# Sheet1.net
KiCad netlist of a schematic drawn in Altium Designer
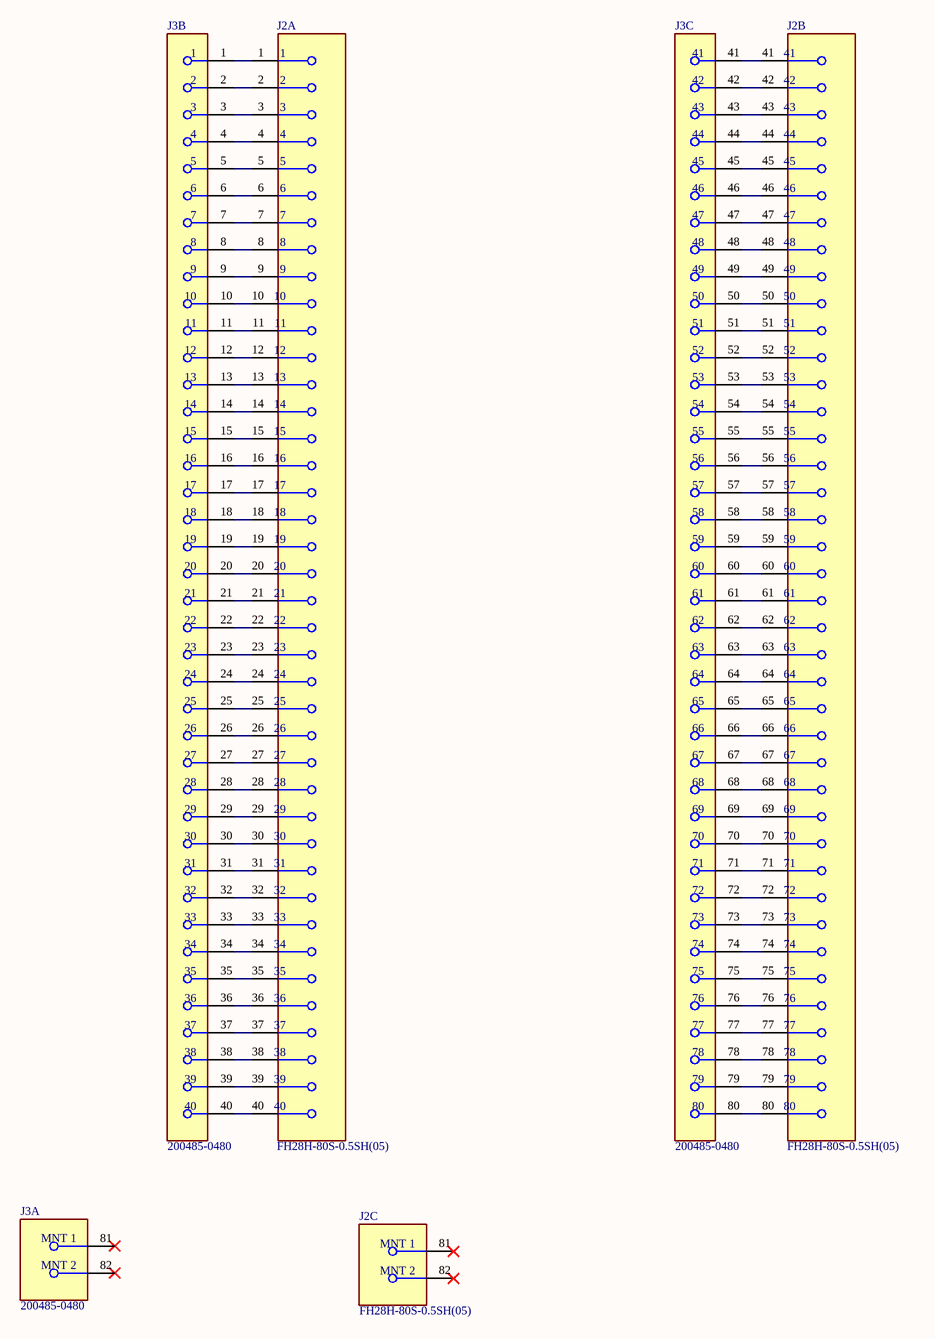
[diagram p0: Sheet1.SchDoc]

(export (version "E")
  (design (tool "Eeschema 10.0.6"))
  (components
    (comp (ref "J2")
      (value "FH28H-80S-0.5SH(05)")
      (footprint "FP-FH28H-80S-0_5SH_05-MFG")
      (description "CONN FFC BOTTOM 80POS 0.50MM R/A")
      (libsource (lib "") (part "08075b3669470a400ec152efcfe4938_1"))
    )
    (comp (ref "J3")
      (value "200485-0480")
      (footprint "FP-200485-0480-MFG")
      (description "0.5 ONE-TOUCH RA 80P")
      (libsource (lib "Altium Content Vault") (part "c44dc25a27ac546c6585fccd4967c56"))
    )
  )
  (nets
    (net (code "1") (name "Net-(J2-Pad1)") (class "Default")
      (node (ref "J2") (pin "1") (pinfunction "1_1") (pintype "passive"))
      (node (ref "J3") (pin "1") (pinfunction "1_1") (pintype "passive"))
    )
    (net (code "2") (name "Net-(J2-Pad2)") (class "Default")
      (node (ref "J2") (pin "2") (pinfunction "2_2") (pintype "passive"))
      (node (ref "J3") (pin "2") (pinfunction "2_2") (pintype "passive"))
    )
    (net (code "3") (name "Net-(J2-Pad3)") (class "Default")
      (node (ref "J2") (pin "3") (pinfunction "3_3") (pintype "passive"))
      (node (ref "J3") (pin "3") (pinfunction "3_3") (pintype "passive"))
    )
    (net (code "4") (name "Net-(J2-Pad4)") (class "Default")
      (node (ref "J2") (pin "4") (pinfunction "4_4") (pintype "passive"))
      (node (ref "J3") (pin "4") (pinfunction "4_4") (pintype "passive"))
    )
    (net (code "5") (name "Net-(J2-Pad5)") (class "Default")
      (node (ref "J2") (pin "5") (pinfunction "5_5") (pintype "passive"))
      (node (ref "J3") (pin "5") (pinfunction "5_5") (pintype "passive"))
    )
    (net (code "6") (name "Net-(J2-Pad6)") (class "Default")
      (node (ref "J2") (pin "6") (pinfunction "6_6") (pintype "passive"))
      (node (ref "J3") (pin "6") (pinfunction "6_6") (pintype "passive"))
    )
    (net (code "7") (name "Net-(J2-Pad7)") (class "Default")
      (node (ref "J2") (pin "7") (pinfunction "7_7") (pintype "passive"))
      (node (ref "J3") (pin "7") (pinfunction "7_7") (pintype "passive"))
    )
    (net (code "8") (name "Net-(J2-Pad8)") (class "Default")
      (node (ref "J2") (pin "8") (pinfunction "8_8") (pintype "passive"))
      (node (ref "J3") (pin "8") (pinfunction "8_8") (pintype "passive"))
    )
    (net (code "9") (name "Net-(J2-Pad9)") (class "Default")
      (node (ref "J2") (pin "9") (pinfunction "9_9") (pintype "passive"))
      (node (ref "J3") (pin "9") (pinfunction "9_9") (pintype "passive"))
    )
    (net (code "10") (name "Net-(J2-Pad10)") (class "Default")
      (node (ref "J2") (pin "10") (pinfunction "10_10") (pintype "passive"))
      (node (ref "J3") (pin "10") (pinfunction "10_10") (pintype "passive"))
    )
    (net (code "11") (name "Net-(J2-Pad11)") (class "Default")
      (node (ref "J2") (pin "11") (pinfunction "11_11") (pintype "passive"))
      (node (ref "J3") (pin "11") (pinfunction "11_11") (pintype "passive"))
    )
    (net (code "12") (name "Net-(J2-Pad12)") (class "Default")
      (node (ref "J2") (pin "12") (pinfunction "12_12") (pintype "passive"))
      (node (ref "J3") (pin "12") (pinfunction "12_12") (pintype "passive"))
    )
    (net (code "13") (name "Net-(J2-Pad13)") (class "Default")
      (node (ref "J2") (pin "13") (pinfunction "13_13") (pintype "passive"))
      (node (ref "J3") (pin "13") (pinfunction "13_13") (pintype "passive"))
    )
    (net (code "14") (name "Net-(J2-Pad14)") (class "Default")
      (node (ref "J2") (pin "14") (pinfunction "14_14") (pintype "passive"))
      (node (ref "J3") (pin "14") (pinfunction "14_14") (pintype "passive"))
    )
    (net (code "15") (name "Net-(J2-Pad15)") (class "Default")
      (node (ref "J2") (pin "15") (pinfunction "15_15") (pintype "passive"))
      (node (ref "J3") (pin "15") (pinfunction "15_15") (pintype "passive"))
    )
    (net (code "16") (name "Net-(J2-Pad16)") (class "Default")
      (node (ref "J2") (pin "16") (pinfunction "16_16") (pintype "passive"))
      (node (ref "J3") (pin "16") (pinfunction "16_16") (pintype "passive"))
    )
    (net (code "17") (name "Net-(J2-Pad17)") (class "Default")
      (node (ref "J2") (pin "17") (pinfunction "17_17") (pintype "passive"))
      (node (ref "J3") (pin "17") (pinfunction "17_17") (pintype "passive"))
    )
    (net (code "18") (name "Net-(J2-Pad18)") (class "Default")
      (node (ref "J2") (pin "18") (pinfunction "18_18") (pintype "passive"))
      (node (ref "J3") (pin "18") (pinfunction "18_18") (pintype "passive"))
    )
    (net (code "19") (name "Net-(J2-Pad19)") (class "Default")
      (node (ref "J2") (pin "19") (pinfunction "19_19") (pintype "passive"))
      (node (ref "J3") (pin "19") (pinfunction "19_19") (pintype "passive"))
    )
    (net (code "20") (name "Net-(J2-Pad20)") (class "Default")
      (node (ref "J2") (pin "20") (pinfunction "20_20") (pintype "passive"))
      (node (ref "J3") (pin "20") (pinfunction "20_20") (pintype "passive"))
    )
    (net (code "21") (name "Net-(J2-Pad21)") (class "Default")
      (node (ref "J2") (pin "21") (pinfunction "21_21") (pintype "passive"))
      (node (ref "J3") (pin "21") (pinfunction "21_21") (pintype "passive"))
    )
    (net (code "22") (name "Net-(J2-Pad22)") (class "Default")
      (node (ref "J2") (pin "22") (pinfunction "22_22") (pintype "passive"))
      (node (ref "J3") (pin "22") (pinfunction "22_22") (pintype "passive"))
    )
    (net (code "23") (name "Net-(J2-Pad23)") (class "Default")
      (node (ref "J2") (pin "23") (pinfunction "23_23") (pintype "passive"))
      (node (ref "J3") (pin "23") (pinfunction "23_23") (pintype "passive"))
    )
    (net (code "24") (name "Net-(J2-Pad24)") (class "Default")
      (node (ref "J2") (pin "24") (pinfunction "24_24") (pintype "passive"))
      (node (ref "J3") (pin "24") (pinfunction "24_24") (pintype "passive"))
    )
    (net (code "25") (name "Net-(J2-Pad25)") (class "Default")
      (node (ref "J2") (pin "25") (pinfunction "25_25") (pintype "passive"))
      (node (ref "J3") (pin "25") (pinfunction "25_25") (pintype "passive"))
    )
    (net (code "26") (name "Net-(J2-Pad26)") (class "Default")
      (node (ref "J2") (pin "26") (pinfunction "26_26") (pintype "passive"))
      (node (ref "J3") (pin "26") (pinfunction "26_26") (pintype "passive"))
    )
    (net (code "27") (name "Net-(J2-Pad27)") (class "Default")
      (node (ref "J2") (pin "27") (pinfunction "27_27") (pintype "passive"))
      (node (ref "J3") (pin "27") (pinfunction "27_27") (pintype "passive"))
    )
    (net (code "28") (name "Net-(J2-Pad28)") (class "Default")
      (node (ref "J2") (pin "28") (pinfunction "28_28") (pintype "passive"))
      (node (ref "J3") (pin "28") (pinfunction "28_28") (pintype "passive"))
    )
    (net (code "29") (name "Net-(J2-Pad29)") (class "Default")
      (node (ref "J2") (pin "29") (pinfunction "29_29") (pintype "passive"))
      (node (ref "J3") (pin "29") (pinfunction "29_29") (pintype "passive"))
    )
    (net (code "30") (name "Net-(J2-Pad30)") (class "Default")
      (node (ref "J2") (pin "30") (pinfunction "30_30") (pintype "passive"))
      (node (ref "J3") (pin "30") (pinfunction "30_30") (pintype "passive"))
    )
    (net (code "31") (name "Net-(J2-Pad31)") (class "Default")
      (node (ref "J2") (pin "31") (pinfunction "31_31") (pintype "passive"))
      (node (ref "J3") (pin "31") (pinfunction "31_31") (pintype "passive"))
    )
    (net (code "32") (name "Net-(J2-Pad32)") (class "Default")
      (node (ref "J2") (pin "32") (pinfunction "32_32") (pintype "passive"))
      (node (ref "J3") (pin "32") (pinfunction "32_32") (pintype "passive"))
    )
    (net (code "33") (name "Net-(J2-Pad33)") (class "Default")
      (node (ref "J2") (pin "33") (pinfunction "33_33") (pintype "passive"))
      (node (ref "J3") (pin "33") (pinfunction "33_33") (pintype "passive"))
    )
    (net (code "34") (name "Net-(J2-Pad34)") (class "Default")
      (node (ref "J2") (pin "34") (pinfunction "34_34") (pintype "passive"))
      (node (ref "J3") (pin "34") (pinfunction "34_34") (pintype "passive"))
    )
    (net (code "35") (name "Net-(J2-Pad35)") (class "Default")
      (node (ref "J2") (pin "35") (pinfunction "35_35") (pintype "passive"))
      (node (ref "J3") (pin "35") (pinfunction "35_35") (pintype "passive"))
    )
    (net (code "36") (name "Net-(J2-Pad36)") (class "Default")
      (node (ref "J2") (pin "36") (pinfunction "36_36") (pintype "passive"))
      (node (ref "J3") (pin "36") (pinfunction "36_36") (pintype "passive"))
    )
    (net (code "37") (name "Net-(J2-Pad37)") (class "Default")
      (node (ref "J2") (pin "37") (pinfunction "37_37") (pintype "passive"))
      (node (ref "J3") (pin "37") (pinfunction "37_37") (pintype "passive"))
    )
    (net (code "38") (name "Net-(J2-Pad38)") (class "Default")
      (node (ref "J2") (pin "38") (pinfunction "38_38") (pintype "passive"))
      (node (ref "J3") (pin "38") (pinfunction "38_38") (pintype "passive"))
    )
    (net (code "39") (name "Net-(J2-Pad39)") (class "Default")
      (node (ref "J2") (pin "39") (pinfunction "39_39") (pintype "passive"))
      (node (ref "J3") (pin "39") (pinfunction "39_39") (pintype "passive"))
    )
    (net (code "40") (name "Net-(J2-Pad40)") (class "Default")
      (node (ref "J2") (pin "40") (pinfunction "40_40") (pintype "passive"))
      (node (ref "J3") (pin "40") (pinfunction "40_40") (pintype "passive"))
    )
    (net (code "41") (name "Net-(J2-Pad41)") (class "Default")
      (node (ref "J2") (pin "41") (pinfunction "41_41") (pintype "passive"))
      (node (ref "J3") (pin "41") (pinfunction "41_41") (pintype "passive"))
    )
    (net (code "42") (name "Net-(J2-Pad42)") (class "Default")
      (node (ref "J2") (pin "42") (pinfunction "42_42") (pintype "passive"))
      (node (ref "J3") (pin "42") (pinfunction "42_42") (pintype "passive"))
    )
    (net (code "43") (name "Net-(J2-Pad43)") (class "Default")
      (node (ref "J2") (pin "43") (pinfunction "43_43") (pintype "passive"))
      (node (ref "J3") (pin "43") (pinfunction "43_43") (pintype "passive"))
    )
    (net (code "44") (name "Net-(J2-Pad44)") (class "Default")
      (node (ref "J2") (pin "44") (pinfunction "44_44") (pintype "passive"))
      (node (ref "J3") (pin "44") (pinfunction "44_44") (pintype "passive"))
    )
    (net (code "45") (name "Net-(J2-Pad45)") (class "Default")
      (node (ref "J2") (pin "45") (pinfunction "45_45") (pintype "passive"))
      (node (ref "J3") (pin "45") (pinfunction "45_45") (pintype "passive"))
    )
    (net (code "46") (name "Net-(J2-Pad46)") (class "Default")
      (node (ref "J2") (pin "46") (pinfunction "46_46") (pintype "passive"))
      (node (ref "J3") (pin "46") (pinfunction "46_46") (pintype "passive"))
    )
    (net (code "47") (name "Net-(J2-Pad47)") (class "Default")
      (node (ref "J2") (pin "47") (pinfunction "47_47") (pintype "passive"))
      (node (ref "J3") (pin "47") (pinfunction "47_47") (pintype "passive"))
    )
    (net (code "48") (name "Net-(J2-Pad48)") (class "Default")
      (node (ref "J2") (pin "48") (pinfunction "48_48") (pintype "passive"))
      (node (ref "J3") (pin "48") (pinfunction "48_48") (pintype "passive"))
    )
    (net (code "49") (name "Net-(J2-Pad49)") (class "Default")
      (node (ref "J2") (pin "49") (pinfunction "49_49") (pintype "passive"))
      (node (ref "J3") (pin "49") (pinfunction "49_49") (pintype "passive"))
    )
    (net (code "50") (name "Net-(J2-Pad50)") (class "Default")
      (node (ref "J2") (pin "50") (pinfunction "50_50") (pintype "passive"))
      (node (ref "J3") (pin "50") (pinfunction "50_50") (pintype "passive"))
    )
    (net (code "51") (name "Net-(J2-Pad51)") (class "Default")
      (node (ref "J2") (pin "51") (pinfunction "51_51") (pintype "passive"))
      (node (ref "J3") (pin "51") (pinfunction "51_51") (pintype "passive"))
    )
    (net (code "52") (name "Net-(J2-Pad52)") (class "Default")
      (node (ref "J2") (pin "52") (pinfunction "52_52") (pintype "passive"))
      (node (ref "J3") (pin "52") (pinfunction "52_52") (pintype "passive"))
    )
    (net (code "53") (name "Net-(J2-Pad53)") (class "Default")
      (node (ref "J2") (pin "53") (pinfunction "53_53") (pintype "passive"))
      (node (ref "J3") (pin "53") (pinfunction "53_53") (pintype "passive"))
    )
    (net (code "54") (name "Net-(J2-Pad54)") (class "Default")
      (node (ref "J2") (pin "54") (pinfunction "54_54") (pintype "passive"))
      (node (ref "J3") (pin "54") (pinfunction "54_54") (pintype "passive"))
    )
    (net (code "55") (name "Net-(J2-Pad55)") (class "Default")
      (node (ref "J2") (pin "55") (pinfunction "55_55") (pintype "passive"))
      (node (ref "J3") (pin "55") (pinfunction "55_55") (pintype "passive"))
    )
    (net (code "56") (name "Net-(J2-Pad56)") (class "Default")
      (node (ref "J2") (pin "56") (pinfunction "56_56") (pintype "passive"))
      (node (ref "J3") (pin "56") (pinfunction "56_56") (pintype "passive"))
    )
    (net (code "57") (name "Net-(J2-Pad57)") (class "Default")
      (node (ref "J2") (pin "57") (pinfunction "57_57") (pintype "passive"))
      (node (ref "J3") (pin "57") (pinfunction "57_57") (pintype "passive"))
    )
    (net (code "58") (name "Net-(J2-Pad58)") (class "Default")
      (node (ref "J2") (pin "58") (pinfunction "58_58") (pintype "passive"))
      (node (ref "J3") (pin "58") (pinfunction "58_58") (pintype "passive"))
    )
    (net (code "59") (name "Net-(J2-Pad59)") (class "Default")
      (node (ref "J2") (pin "59") (pinfunction "59_59") (pintype "passive"))
      (node (ref "J3") (pin "59") (pinfunction "59_59") (pintype "passive"))
    )
    (net (code "60") (name "Net-(J2-Pad60)") (class "Default")
      (node (ref "J2") (pin "60") (pinfunction "60_60") (pintype "passive"))
      (node (ref "J3") (pin "60") (pinfunction "60_60") (pintype "passive"))
    )
    (net (code "61") (name "Net-(J2-Pad61)") (class "Default")
      (node (ref "J2") (pin "61") (pinfunction "61_61") (pintype "passive"))
      (node (ref "J3") (pin "61") (pinfunction "61_61") (pintype "passive"))
    )
    (net (code "62") (name "Net-(J2-Pad62)") (class "Default")
      (node (ref "J2") (pin "62") (pinfunction "62_62") (pintype "passive"))
      (node (ref "J3") (pin "62") (pinfunction "62_62") (pintype "passive"))
    )
    (net (code "63") (name "Net-(J2-Pad63)") (class "Default")
      (node (ref "J2") (pin "63") (pinfunction "63_63") (pintype "passive"))
      (node (ref "J3") (pin "63") (pinfunction "63_63") (pintype "passive"))
    )
    (net (code "64") (name "Net-(J2-Pad64)") (class "Default")
      (node (ref "J2") (pin "64") (pinfunction "64_64") (pintype "passive"))
      (node (ref "J3") (pin "64") (pinfunction "64_64") (pintype "passive"))
    )
    (net (code "65") (name "Net-(J2-Pad65)") (class "Default")
      (node (ref "J2") (pin "65") (pinfunction "65_65") (pintype "passive"))
      (node (ref "J3") (pin "65") (pinfunction "65_65") (pintype "passive"))
    )
    (net (code "66") (name "Net-(J2-Pad66)") (class "Default")
      (node (ref "J2") (pin "66") (pinfunction "66_66") (pintype "passive"))
      (node (ref "J3") (pin "66") (pinfunction "66_66") (pintype "passive"))
    )
    (net (code "67") (name "Net-(J2-Pad67)") (class "Default")
      (node (ref "J2") (pin "67") (pinfunction "67_67") (pintype "passive"))
      (node (ref "J3") (pin "67") (pinfunction "67_67") (pintype "passive"))
    )
    (net (code "68") (name "Net-(J2-Pad68)") (class "Default")
      (node (ref "J2") (pin "68") (pinfunction "68_68") (pintype "passive"))
      (node (ref "J3") (pin "68") (pinfunction "68_68") (pintype "passive"))
    )
    (net (code "69") (name "Net-(J2-Pad69)") (class "Default")
      (node (ref "J2") (pin "69") (pinfunction "69_69") (pintype "passive"))
      (node (ref "J3") (pin "69") (pinfunction "69_69") (pintype "passive"))
    )
    (net (code "70") (name "Net-(J2-Pad70)") (class "Default")
      (node (ref "J2") (pin "70") (pinfunction "70_70") (pintype "passive"))
      (node (ref "J3") (pin "70") (pinfunction "70_70") (pintype "passive"))
    )
    (net (code "71") (name "Net-(J2-Pad71)") (class "Default")
      (node (ref "J2") (pin "71") (pinfunction "71_71") (pintype "passive"))
      (node (ref "J3") (pin "71") (pinfunction "71_71") (pintype "passive"))
    )
    (net (code "72") (name "Net-(J2-Pad72)") (class "Default")
      (node (ref "J2") (pin "72") (pinfunction "72_72") (pintype "passive"))
      (node (ref "J3") (pin "72") (pinfunction "72_72") (pintype "passive"))
    )
    (net (code "73") (name "Net-(J2-Pad73)") (class "Default")
      (node (ref "J2") (pin "73") (pinfunction "73_73") (pintype "passive"))
      (node (ref "J3") (pin "73") (pinfunction "73_73") (pintype "passive"))
    )
    (net (code "74") (name "Net-(J2-Pad74)") (class "Default")
      (node (ref "J2") (pin "74") (pinfunction "74_74") (pintype "passive"))
      (node (ref "J3") (pin "74") (pinfunction "74_74") (pintype "passive"))
    )
    (net (code "75") (name "Net-(J2-Pad75)") (class "Default")
      (node (ref "J2") (pin "75") (pinfunction "75_75") (pintype "passive"))
      (node (ref "J3") (pin "75") (pinfunction "75_75") (pintype "passive"))
    )
    (net (code "76") (name "Net-(J2-Pad76)") (class "Default")
      (node (ref "J2") (pin "76") (pinfunction "76_76") (pintype "passive"))
      (node (ref "J3") (pin "76") (pinfunction "76_76") (pintype "passive"))
    )
    (net (code "77") (name "Net-(J2-Pad77)") (class "Default")
      (node (ref "J2") (pin "77") (pinfunction "77_77") (pintype "passive"))
      (node (ref "J3") (pin "77") (pinfunction "77_77") (pintype "passive"))
    )
    (net (code "78") (name "Net-(J2-Pad78)") (class "Default")
      (node (ref "J2") (pin "78") (pinfunction "78_78") (pintype "passive"))
      (node (ref "J3") (pin "78") (pinfunction "78_78") (pintype "passive"))
    )
    (net (code "79") (name "Net-(J2-Pad79)") (class "Default")
      (node (ref "J2") (pin "79") (pinfunction "79_79") (pintype "passive"))
      (node (ref "J3") (pin "79") (pinfunction "79_79") (pintype "passive"))
    )
    (net (code "80") (name "Net-(J2-Pad80)") (class "Default")
      (node (ref "J2") (pin "80") (pinfunction "80_80") (pintype "passive"))
      (node (ref "J3") (pin "80") (pinfunction "80_80") (pintype "passive"))
    )
    (net (code "81") (name "unconnected-(J2C-MNT_1-Pad81)") (class "Default")
      (node (ref "J2") (pin "81") (pinfunction "MNT_1_81") (pintype "passive+no_connect"))
    )
    (net (code "82") (name "unconnected-(J2C-MNT_2-Pad82)") (class "Default")
      (node (ref "J2") (pin "82") (pinfunction "MNT_2_82") (pintype "passive+no_connect"))
    )
    (net (code "83") (name "unconnected-(J3A-MNT_1-Pad81)") (class "Default")
      (node (ref "J3") (pin "81") (pinfunction "MNT_1_81") (pintype "passive+no_connect"))
    )
    (net (code "84") (name "unconnected-(J3A-MNT_2-Pad82)") (class "Default")
      (node (ref "J3") (pin "82") (pinfunction "MNT_2_82") (pintype "passive+no_connect"))
    )
  )
)
